# Versatile_IO_Card.net
KiCad netlist of a schematic drawn in EAGLE
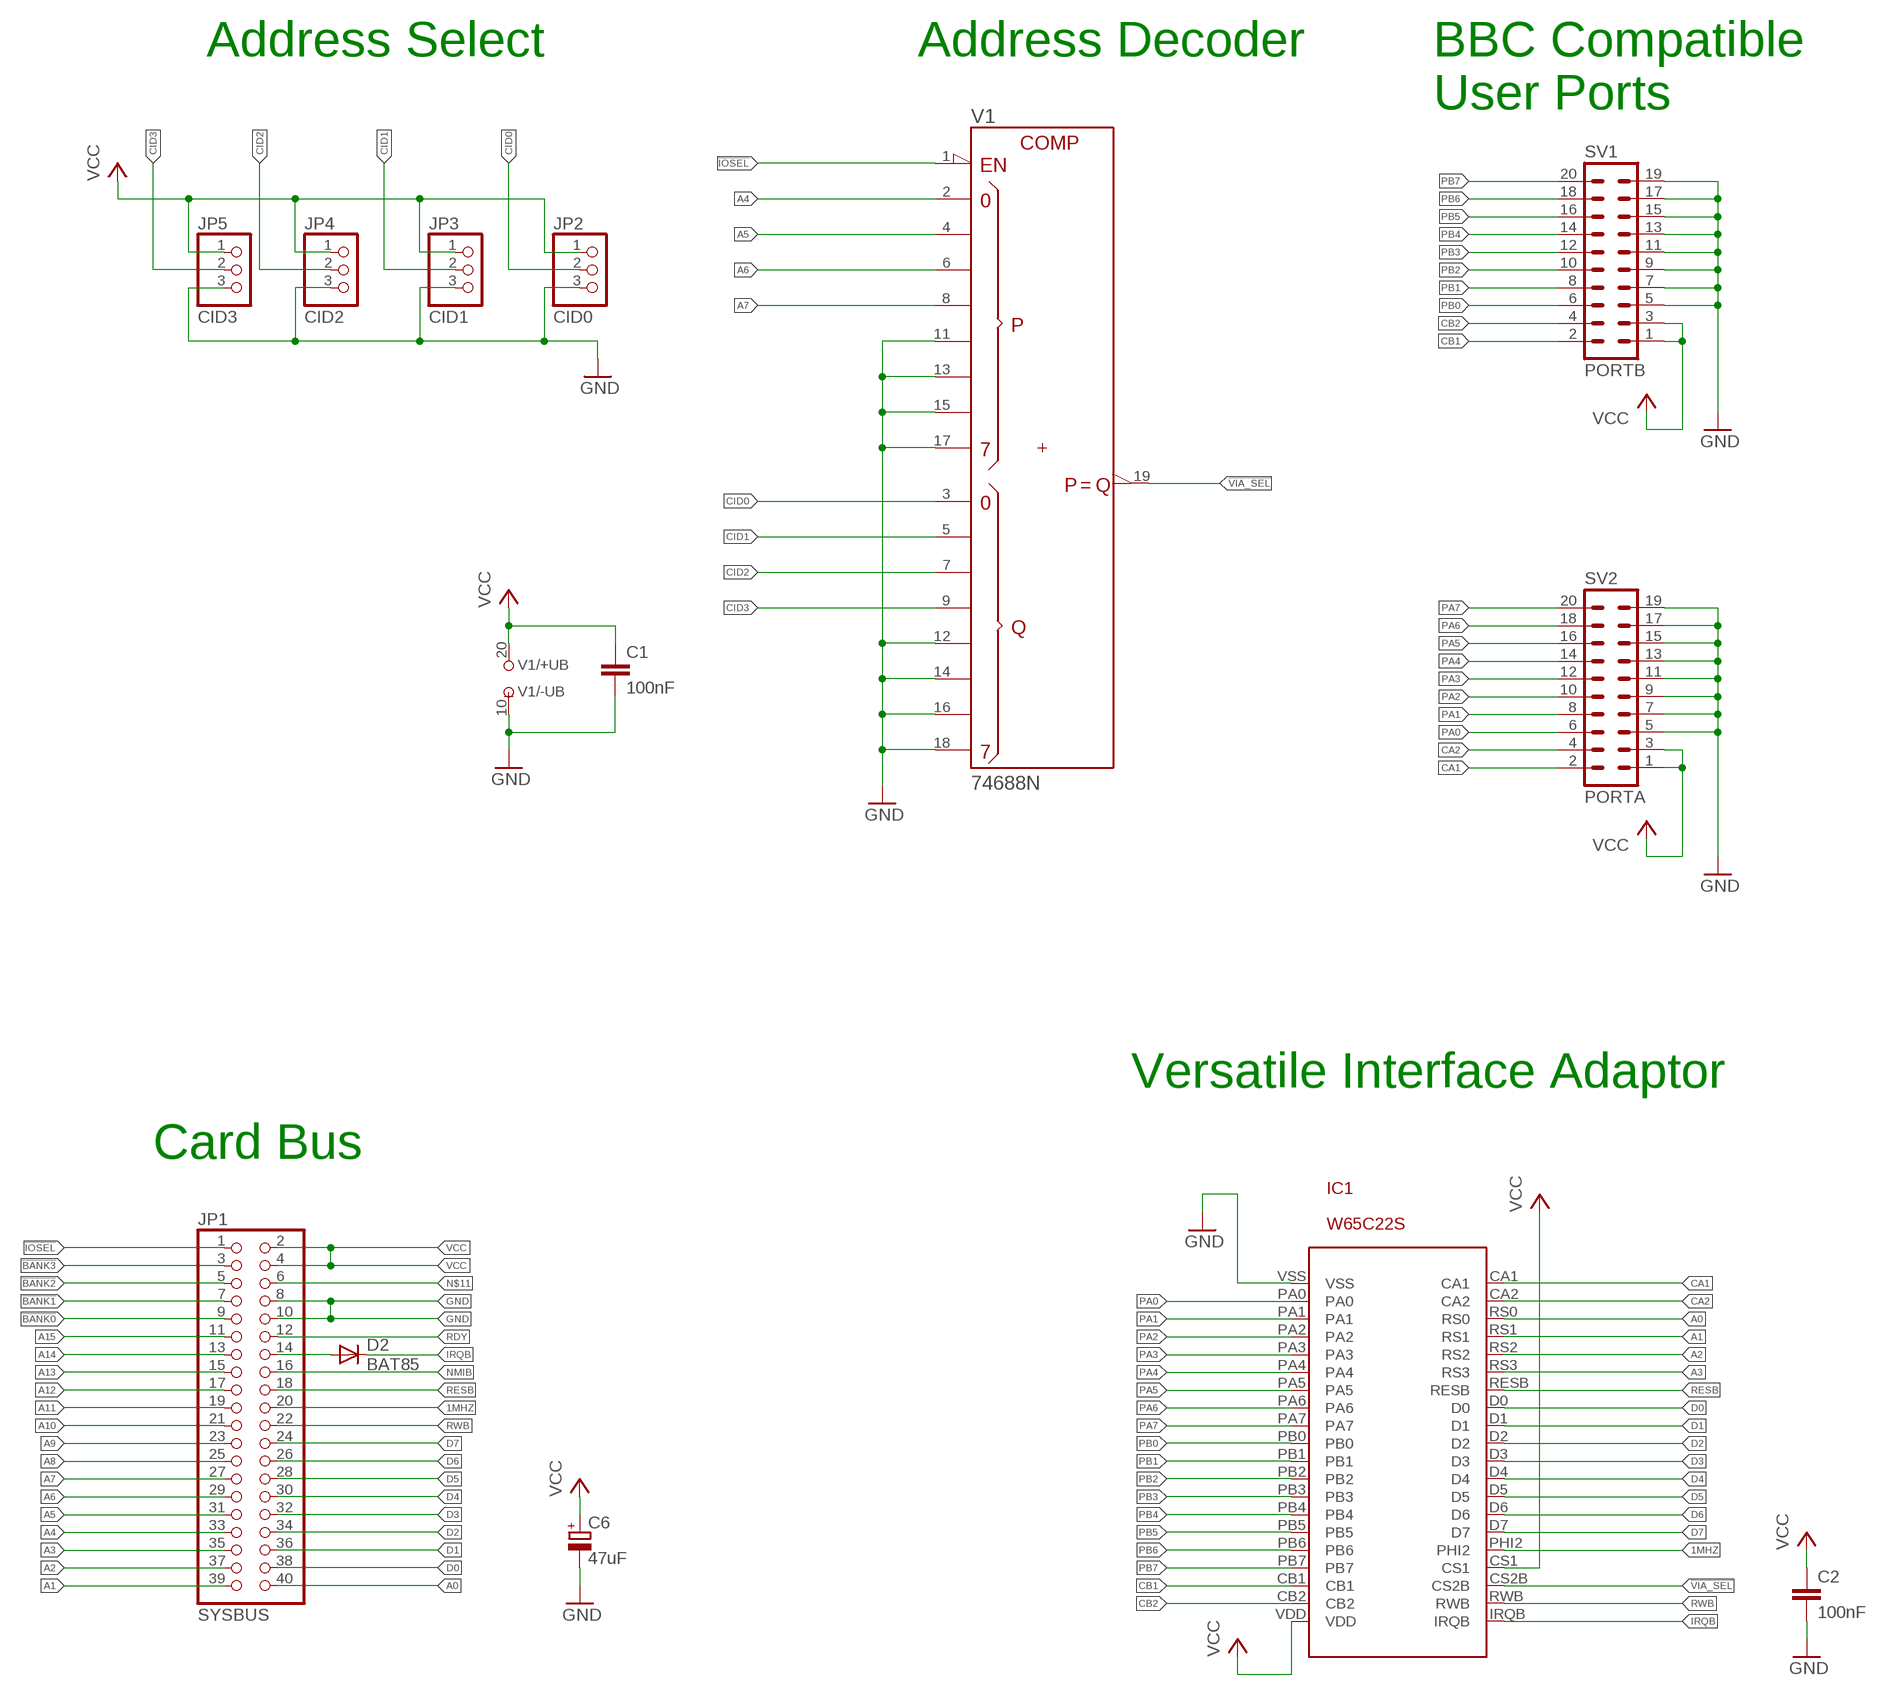
[diagram p0: schematic, sheet 1]

(export (version "E")
  (design (tool "Eeschema 10.0.6"))
  (components
    (comp (ref "C1")
      (value "100nF")
      (footprint "eagle-import:C050-025X075")
      (libsource (lib "eagle-import") (part "C-EU050-025X075"))
    )
    (comp (ref "C2")
      (value "100nF")
      (footprint "eagle-import:C050-025X075")
      (libsource (lib "eagle-import") (part "C-EU050-025X075"))
    )
    (comp (ref "C6")
      (value "47uF")
      (footprint "eagle-import:E2,5-7")
      (libsource (lib "eagle-import") (part "CPOL-EUE2.5-7"))
    )
    (comp (ref "D2")
      (value "BAT85")
      (footprint "eagle-import:DO34-7")
      (libsource (lib "eagle-import") (part "BAT81"))
    )
    (comp (ref "IC1")
      (value "W65C22S")
      (footprint "eagle-import:W65C22-DIP")
      (libsource (lib "eagle-import") (part "W65C22"))
    )
    (comp (ref "JP1")
      (value "SYSBUS")
      (footprint "eagle-import:2X20_90")
      (libsource (lib "eagle-import") (part "PINHD-2X20/90"))
    )
    (comp (ref "JP2")
      (value "CID0")
      (footprint "eagle-import:1X03")
      (libsource (lib "eagle-import") (part "PINHD-1X3"))
    )
    (comp (ref "JP3")
      (value "CID1")
      (footprint "eagle-import:1X03")
      (libsource (lib "eagle-import") (part "PINHD-1X3"))
    )
    (comp (ref "JP4")
      (value "CID2")
      (footprint "eagle-import:1X03")
      (libsource (lib "eagle-import") (part "PINHD-1X3"))
    )
    (comp (ref "JP5")
      (value "CID3")
      (footprint "eagle-import:1X03")
      (libsource (lib "eagle-import") (part "PINHD-1X3"))
    )
    (comp (ref "SV1")
      (value "PORTB")
      (footprint "eagle-import:ML20L")
      (libsource (lib "eagle-import") (part "ML20L"))
    )
    (comp (ref "SV2")
      (value "PORTA")
      (footprint "eagle-import:ML20L")
      (libsource (lib "eagle-import") (part "ML20L"))
    )
    (comp (ref "V1")
      (value "74688N")
      (footprint "eagle-import:DIL20")
      (libsource (lib "eagle-import") (part "74688N"))
    )
  )
  (nets
    (net (code "1") (name "/~{BANK0}") (class "Default")
      (node (ref "JP1") (pin "9") (pinfunction "9_9") (pintype "passive"))
    )
    (net (code "2") (name "/~{BANK1}") (class "Default")
      (node (ref "JP1") (pin "7") (pinfunction "7_7") (pintype "passive"))
    )
    (net (code "3") (name "/~{BANK2}") (class "Default")
      (node (ref "JP1") (pin "5") (pinfunction "5_5") (pintype "passive"))
    )
    (net (code "4") (name "/~{BANK3}") (class "Default")
      (node (ref "JP1") (pin "3") (pinfunction "3_3") (pintype "passive"))
    )
    (net (code "5") (name "/~{IOSEL}") (class "Default")
      (node (ref "JP1") (pin "1") (pinfunction "1_1") (pintype "passive"))
      (node (ref "V1") (pin "1") (pinfunction "~{G}_1") (pintype "input"))
    )
    (net (code "6") (name "/~{VIA_SEL}") (class "Default")
      (node (ref "IC1") (pin "CS2B") (pinfunction "CS2B_CS2B") (pintype "bidirectional"))
      (node (ref "V1") (pin "19") (pinfunction "~{P=Q}_19") (pintype "output"))
    )
    (net (code "7") (name "1MHZ") (class "Default")
      (node (ref "IC1") (pin "PHI2") (pinfunction "PHI2_PHI2") (pintype "input"))
      (node (ref "JP1") (pin "20") (pinfunction "20_20") (pintype "passive"))
    )
    (net (code "8") (name "A0") (class "Default")
      (node (ref "IC1") (pin "RS0") (pinfunction "RS0_RS0") (pintype "input"))
      (node (ref "JP1") (pin "40") (pinfunction "40_40") (pintype "passive"))
    )
    (net (code "9") (name "A1") (class "Default")
      (node (ref "IC1") (pin "RS1") (pinfunction "RS1_RS1") (pintype "input"))
      (node (ref "JP1") (pin "39") (pinfunction "39_39") (pintype "passive"))
    )
    (net (code "10") (name "A2") (class "Default")
      (node (ref "IC1") (pin "RS2") (pinfunction "RS2_RS2") (pintype "input"))
      (node (ref "JP1") (pin "37") (pinfunction "37_37") (pintype "passive"))
    )
    (net (code "11") (name "A3") (class "Default")
      (node (ref "IC1") (pin "RS3") (pinfunction "RS3_RS3") (pintype "input"))
      (node (ref "JP1") (pin "35") (pinfunction "35_35") (pintype "passive"))
    )
    (net (code "12") (name "A4") (class "Default")
      (node (ref "JP1") (pin "33") (pinfunction "33_33") (pintype "passive"))
      (node (ref "V1") (pin "2") (pinfunction "P0_2") (pintype "input"))
    )
    (net (code "13") (name "A5") (class "Default")
      (node (ref "JP1") (pin "31") (pinfunction "31_31") (pintype "passive"))
      (node (ref "V1") (pin "4") (pinfunction "P1_4") (pintype "input"))
    )
    (net (code "14") (name "A6") (class "Default")
      (node (ref "JP1") (pin "29") (pinfunction "29_29") (pintype "passive"))
      (node (ref "V1") (pin "6") (pinfunction "P2_6") (pintype "input"))
    )
    (net (code "15") (name "A7") (class "Default")
      (node (ref "JP1") (pin "27") (pinfunction "27_27") (pintype "passive"))
      (node (ref "V1") (pin "8") (pinfunction "P3_8") (pintype "input"))
    )
    (net (code "16") (name "A8") (class "Default")
      (node (ref "JP1") (pin "25") (pinfunction "25_25") (pintype "passive"))
    )
    (net (code "17") (name "A9") (class "Default")
      (node (ref "JP1") (pin "23") (pinfunction "23_23") (pintype "passive"))
    )
    (net (code "18") (name "A10") (class "Default")
      (node (ref "JP1") (pin "21") (pinfunction "21_21") (pintype "passive"))
    )
    (net (code "19") (name "A11") (class "Default")
      (node (ref "JP1") (pin "19") (pinfunction "19_19") (pintype "passive"))
    )
    (net (code "20") (name "A12") (class "Default")
      (node (ref "JP1") (pin "17") (pinfunction "17_17") (pintype "passive"))
    )
    (net (code "21") (name "A13") (class "Default")
      (node (ref "JP1") (pin "15") (pinfunction "15_15") (pintype "passive"))
    )
    (net (code "22") (name "A14") (class "Default")
      (node (ref "JP1") (pin "13") (pinfunction "13_13") (pintype "passive"))
    )
    (net (code "23") (name "A15") (class "Default")
      (node (ref "JP1") (pin "11") (pinfunction "11_11") (pintype "passive"))
    )
    (net (code "24") (name "CA1") (class "Default")
      (node (ref "IC1") (pin "CA1") (pinfunction "CA1_CA1") (pintype "bidirectional"))
      (node (ref "SV2") (pin "2") (pinfunction "2_2") (pintype "passive"))
    )
    (net (code "25") (name "CA2") (class "Default")
      (node (ref "IC1") (pin "CA2") (pinfunction "CA2_CA2") (pintype "bidirectional"))
      (node (ref "SV2") (pin "4") (pinfunction "4_4") (pintype "passive"))
    )
    (net (code "26") (name "CB1") (class "Default")
      (node (ref "IC1") (pin "CB1") (pinfunction "CB1_CB1") (pintype "bidirectional"))
      (node (ref "SV1") (pin "2") (pinfunction "2_2") (pintype "passive"))
    )
    (net (code "27") (name "CB2") (class "Default")
      (node (ref "IC1") (pin "CB2") (pinfunction "CB2_CB2") (pintype "bidirectional"))
      (node (ref "SV1") (pin "4") (pinfunction "4_4") (pintype "passive"))
    )
    (net (code "28") (name "CID0") (class "Default")
      (node (ref "JP2") (pin "2") (pinfunction "2_2") (pintype "passive"))
      (node (ref "V1") (pin "3") (pinfunction "Q0_3") (pintype "input"))
    )
    (net (code "29") (name "CID1") (class "Default")
      (node (ref "JP3") (pin "2") (pinfunction "2_2") (pintype "passive"))
      (node (ref "V1") (pin "5") (pinfunction "Q1_5") (pintype "input"))
    )
    (net (code "30") (name "CID2") (class "Default")
      (node (ref "JP4") (pin "2") (pinfunction "2_2") (pintype "passive"))
      (node (ref "V1") (pin "7") (pinfunction "Q2_7") (pintype "input"))
    )
    (net (code "31") (name "CID3") (class "Default")
      (node (ref "JP5") (pin "2") (pinfunction "2_2") (pintype "passive"))
      (node (ref "V1") (pin "9") (pinfunction "Q3_9") (pintype "input"))
    )
    (net (code "32") (name "D0") (class "Default")
      (node (ref "IC1") (pin "D0") (pinfunction "D0_D0") (pintype "bidirectional"))
      (node (ref "JP1") (pin "38") (pinfunction "38_38") (pintype "passive"))
    )
    (net (code "33") (name "D1") (class "Default")
      (node (ref "IC1") (pin "D1") (pinfunction "D1_D1") (pintype "bidirectional"))
      (node (ref "JP1") (pin "36") (pinfunction "36_36") (pintype "passive"))
    )
    (net (code "34") (name "D2") (class "Default")
      (node (ref "IC1") (pin "D2") (pinfunction "D2_D2") (pintype "bidirectional"))
      (node (ref "JP1") (pin "34") (pinfunction "34_34") (pintype "passive"))
    )
    (net (code "35") (name "D3") (class "Default")
      (node (ref "IC1") (pin "D3") (pinfunction "D3_D3") (pintype "bidirectional"))
      (node (ref "JP1") (pin "32") (pinfunction "32_32") (pintype "passive"))
    )
    (net (code "36") (name "D4") (class "Default")
      (node (ref "IC1") (pin "D4") (pinfunction "D4_D4") (pintype "bidirectional"))
      (node (ref "JP1") (pin "30") (pinfunction "30_30") (pintype "passive"))
    )
    (net (code "37") (name "D5") (class "Default")
      (node (ref "IC1") (pin "D5") (pinfunction "D5_D5") (pintype "bidirectional"))
      (node (ref "JP1") (pin "28") (pinfunction "28_28") (pintype "passive"))
    )
    (net (code "38") (name "D6") (class "Default")
      (node (ref "IC1") (pin "D6") (pinfunction "D6_D6") (pintype "bidirectional"))
      (node (ref "JP1") (pin "26") (pinfunction "26_26") (pintype "passive"))
    )
    (net (code "39") (name "D7") (class "Default")
      (node (ref "IC1") (pin "D7") (pinfunction "D7_D7") (pintype "bidirectional"))
      (node (ref "JP1") (pin "24") (pinfunction "24_24") (pintype "passive"))
    )
    (net (code "40") (name "GND") (class "Default")
      (node (ref "C1") (pin "2") (pinfunction "2_2") (pintype "passive"))
      (node (ref "C2") (pin "2") (pinfunction "2_2") (pintype "passive"))
      (node (ref "C6") (pin "-") (pinfunction "-_-") (pintype "passive"))
      (node (ref "IC1") (pin "VSS") (pinfunction "VSS_VSS") (pintype "power_in"))
      (node (ref "JP1") (pin "10") (pinfunction "10_10") (pintype "passive"))
      (node (ref "JP1") (pin "8") (pinfunction "8_8") (pintype "passive"))
      (node (ref "JP2") (pin "3") (pinfunction "3_3") (pintype "passive"))
      (node (ref "JP3") (pin "3") (pinfunction "3_3") (pintype "passive"))
      (node (ref "JP4") (pin "3") (pinfunction "3_3") (pintype "passive"))
      (node (ref "JP5") (pin "3") (pinfunction "3_3") (pintype "passive"))
      (node (ref "SV1") (pin "11") (pinfunction "11_11") (pintype "passive"))
      (node (ref "SV1") (pin "13") (pinfunction "13_13") (pintype "passive"))
      (node (ref "SV1") (pin "15") (pinfunction "15_15") (pintype "passive"))
      (node (ref "SV1") (pin "17") (pinfunction "17_17") (pintype "passive"))
      (node (ref "SV1") (pin "19") (pinfunction "19_19") (pintype "passive"))
      (node (ref "SV1") (pin "5") (pinfunction "5_5") (pintype "passive"))
      (node (ref "SV1") (pin "7") (pinfunction "7_7") (pintype "passive"))
      (node (ref "SV1") (pin "9") (pinfunction "9_9") (pintype "passive"))
      (node (ref "SV2") (pin "11") (pinfunction "11_11") (pintype "passive"))
      (node (ref "SV2") (pin "13") (pinfunction "13_13") (pintype "passive"))
      (node (ref "SV2") (pin "15") (pinfunction "15_15") (pintype "passive"))
      (node (ref "SV2") (pin "17") (pinfunction "17_17") (pintype "passive"))
      (node (ref "SV2") (pin "19") (pinfunction "19_19") (pintype "passive"))
      (node (ref "SV2") (pin "5") (pinfunction "5_5") (pintype "passive"))
      (node (ref "SV2") (pin "7") (pinfunction "7_7") (pintype "passive"))
      (node (ref "SV2") (pin "9") (pinfunction "9_9") (pintype "passive"))
      (node (ref "V1") (pin "10") (pinfunction "-UB_10") (pintype "power_in"))
      (node (ref "V1") (pin "11") (pinfunction "P4_11") (pintype "input"))
      (node (ref "V1") (pin "12") (pinfunction "Q4_12") (pintype "input"))
      (node (ref "V1") (pin "13") (pinfunction "P5_13") (pintype "input"))
      (node (ref "V1") (pin "14") (pinfunction "Q5_14") (pintype "input"))
      (node (ref "V1") (pin "15") (pinfunction "P6_15") (pintype "input"))
      (node (ref "V1") (pin "16") (pinfunction "Q6_16") (pintype "input"))
      (node (ref "V1") (pin "17") (pinfunction "P7_17") (pintype "input"))
      (node (ref "V1") (pin "18") (pinfunction "Q7_18") (pintype "input"))
    )
    (net (code "41") (name "IRQB") (class "Default")
      (node (ref "D2") (pin "C") (pinfunction "C_C") (pintype "passive"))
      (node (ref "IC1") (pin "IRQB") (pinfunction "IRQB_IRQB") (pintype "output"))
    )
    (net (code "42") (name "N$11") (class "Default")
      (node (ref "JP1") (pin "6") (pinfunction "6_6") (pintype "passive"))
    )
    (net (code "43") (name "NMIB") (class "Default")
      (node (ref "JP1") (pin "16") (pinfunction "16_16") (pintype "passive"))
    )
    (net (code "44") (name "Net-(D2-PadA)") (class "Default")
      (node (ref "D2") (pin "A") (pinfunction "A_A") (pintype "passive"))
      (node (ref "JP1") (pin "14") (pinfunction "14_14") (pintype "passive"))
    )
    (net (code "45") (name "PA0") (class "Default")
      (node (ref "IC1") (pin "PA0") (pinfunction "PA0_PA0") (pintype "bidirectional"))
      (node (ref "SV2") (pin "6") (pinfunction "6_6") (pintype "passive"))
    )
    (net (code "46") (name "PA1") (class "Default")
      (node (ref "IC1") (pin "PA1") (pinfunction "PA1_PA1") (pintype "bidirectional"))
      (node (ref "SV2") (pin "8") (pinfunction "8_8") (pintype "passive"))
    )
    (net (code "47") (name "PA2") (class "Default")
      (node (ref "IC1") (pin "PA2") (pinfunction "PA2_PA2") (pintype "bidirectional"))
      (node (ref "SV2") (pin "10") (pinfunction "10_10") (pintype "passive"))
    )
    (net (code "48") (name "PA3") (class "Default")
      (node (ref "IC1") (pin "PA3") (pinfunction "PA3_PA3") (pintype "bidirectional"))
      (node (ref "SV2") (pin "12") (pinfunction "12_12") (pintype "passive"))
    )
    (net (code "49") (name "PA4") (class "Default")
      (node (ref "IC1") (pin "PA4") (pinfunction "PA4_PA4") (pintype "bidirectional"))
      (node (ref "SV2") (pin "14") (pinfunction "14_14") (pintype "passive"))
    )
    (net (code "50") (name "PA5") (class "Default")
      (node (ref "IC1") (pin "PA5") (pinfunction "PA5_PA5") (pintype "bidirectional"))
      (node (ref "SV2") (pin "16") (pinfunction "16_16") (pintype "passive"))
    )
    (net (code "51") (name "PA6") (class "Default")
      (node (ref "IC1") (pin "PA6") (pinfunction "PA6_PA6") (pintype "bidirectional"))
      (node (ref "SV2") (pin "18") (pinfunction "18_18") (pintype "passive"))
    )
    (net (code "52") (name "PA7") (class "Default")
      (node (ref "IC1") (pin "PA7") (pinfunction "PA7_PA7") (pintype "bidirectional"))
      (node (ref "SV2") (pin "20") (pinfunction "20_20") (pintype "passive"))
    )
    (net (code "53") (name "PB0") (class "Default")
      (node (ref "IC1") (pin "PB0") (pinfunction "PB0_PB0") (pintype "bidirectional"))
      (node (ref "SV1") (pin "6") (pinfunction "6_6") (pintype "passive"))
    )
    (net (code "54") (name "PB1") (class "Default")
      (node (ref "IC1") (pin "PB1") (pinfunction "PB1_PB1") (pintype "bidirectional"))
      (node (ref "SV1") (pin "8") (pinfunction "8_8") (pintype "passive"))
    )
    (net (code "55") (name "PB2") (class "Default")
      (node (ref "IC1") (pin "PB2") (pinfunction "PB2_PB2") (pintype "bidirectional"))
      (node (ref "SV1") (pin "10") (pinfunction "10_10") (pintype "passive"))
    )
    (net (code "56") (name "PB3") (class "Default")
      (node (ref "IC1") (pin "PB3") (pinfunction "PB3_PB3") (pintype "bidirectional"))
      (node (ref "SV1") (pin "12") (pinfunction "12_12") (pintype "passive"))
    )
    (net (code "57") (name "PB4") (class "Default")
      (node (ref "IC1") (pin "PB4") (pinfunction "PB4_PB4") (pintype "bidirectional"))
      (node (ref "SV1") (pin "14") (pinfunction "14_14") (pintype "passive"))
    )
    (net (code "58") (name "PB5") (class "Default")
      (node (ref "IC1") (pin "PB5") (pinfunction "PB5_PB5") (pintype "bidirectional"))
      (node (ref "SV1") (pin "16") (pinfunction "16_16") (pintype "passive"))
    )
    (net (code "59") (name "PB6") (class "Default")
      (node (ref "IC1") (pin "PB6") (pinfunction "PB6_PB6") (pintype "bidirectional"))
      (node (ref "SV1") (pin "18") (pinfunction "18_18") (pintype "passive"))
    )
    (net (code "60") (name "PB7") (class "Default")
      (node (ref "IC1") (pin "PB7") (pinfunction "PB7_PB7") (pintype "bidirectional"))
      (node (ref "SV1") (pin "20") (pinfunction "20_20") (pintype "passive"))
    )
    (net (code "61") (name "RDY") (class "Default")
      (node (ref "JP1") (pin "12") (pinfunction "12_12") (pintype "passive"))
    )
    (net (code "62") (name "RESB") (class "Default")
      (node (ref "IC1") (pin "RESB") (pinfunction "RESB_RESB") (pintype "input"))
      (node (ref "JP1") (pin "18") (pinfunction "18_18") (pintype "passive"))
    )
    (net (code "63") (name "RWB") (class "Default")
      (node (ref "IC1") (pin "RWB") (pinfunction "RWB_RWB") (pintype "input"))
      (node (ref "JP1") (pin "22") (pinfunction "22_22") (pintype "passive"))
    )
    (net (code "64") (name "VCC") (class "Default")
      (node (ref "C1") (pin "1") (pinfunction "1_1") (pintype "passive"))
      (node (ref "C2") (pin "1") (pinfunction "1_1") (pintype "passive"))
      (node (ref "C6") (pin "+") (pinfunction "+_+") (pintype "passive"))
      (node (ref "IC1") (pin "CS1") (pinfunction "CS1_CS1") (pintype "bidirectional"))
      (node (ref "IC1") (pin "VDD") (pinfunction "VDD_VDD") (pintype "power_in"))
      (node (ref "JP1") (pin "2") (pinfunction "2_2") (pintype "passive"))
      (node (ref "JP1") (pin "4") (pinfunction "4_4") (pintype "passive"))
      (node (ref "JP2") (pin "1") (pinfunction "1_1") (pintype "passive"))
      (node (ref "JP3") (pin "1") (pinfunction "1_1") (pintype "passive"))
      (node (ref "JP4") (pin "1") (pinfunction "1_1") (pintype "passive"))
      (node (ref "JP5") (pin "1") (pinfunction "1_1") (pintype "passive"))
      (node (ref "SV1") (pin "1") (pinfunction "1_1") (pintype "passive"))
      (node (ref "SV1") (pin "3") (pinfunction "3_3") (pintype "passive"))
      (node (ref "SV2") (pin "1") (pinfunction "1_1") (pintype "passive"))
      (node (ref "SV2") (pin "3") (pinfunction "3_3") (pintype "passive"))
      (node (ref "V1") (pin "20") (pinfunction "+UB_20") (pintype "power_in"))
    )
  )
)
